# CANFLYSKY.net
KiCad netlist of a schematic drawn in EAGLE
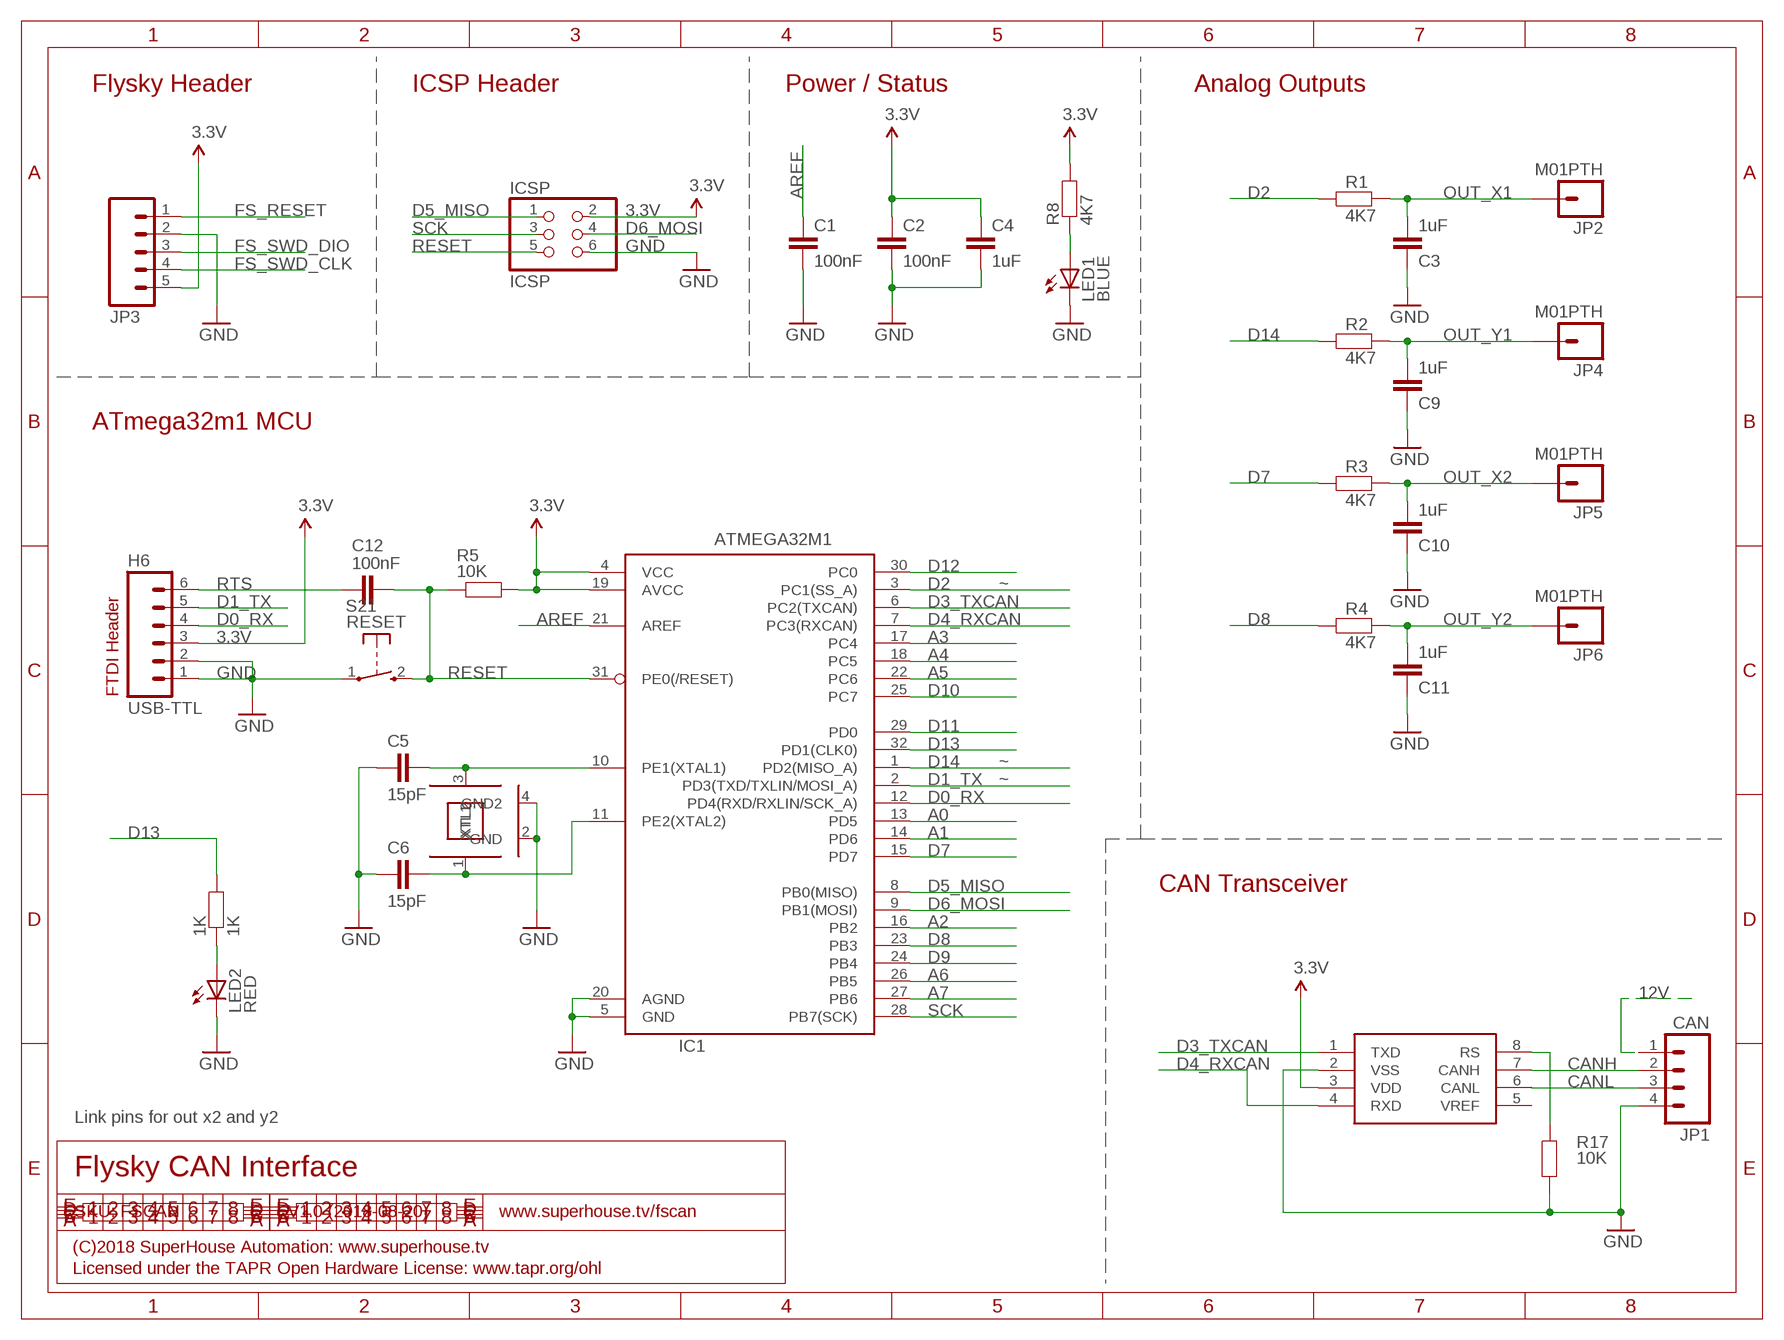
[diagram p0: schematic, sheet 1]

(export (version "E")
  (design (tool "Eeschema 10.0.6"))
  (components
    (comp (ref "1K")
      (value "1K")
      (footprint "eagle-import:0603")
      (libsource (lib "eagle-import") (part "RESISTOR0603"))
    )
    (comp (ref "C1")
      (value "100nF")
      (footprint "eagle-import:0603")
      (libsource (lib "eagle-import") (part "CAP0603"))
    )
    (comp (ref "C2")
      (value "100nF")
      (footprint "eagle-import:0603")
      (libsource (lib "eagle-import") (part "CAP0603"))
    )
    (comp (ref "C3")
      (value "1uF")
      (footprint "eagle-import:0603")
      (libsource (lib "eagle-import") (part "CAP0603"))
    )
    (comp (ref "C4")
      (value "1uF")
      (footprint "eagle-import:0603")
      (libsource (lib "eagle-import") (part "CAP0603"))
    )
    (comp (ref "C5")
      (value "15pF")
      (footprint "eagle-import:0603")
      (libsource (lib "eagle-import") (part "CAP0603"))
    )
    (comp (ref "C6")
      (value "15pF")
      (footprint "eagle-import:0603")
      (libsource (lib "eagle-import") (part "CAP0603"))
    )
    (comp (ref "C9")
      (value "1uF")
      (footprint "eagle-import:0603")
      (libsource (lib "eagle-import") (part "CAP0603"))
    )
    (comp (ref "C10")
      (value "1uF")
      (footprint "eagle-import:0603")
      (libsource (lib "eagle-import") (part "CAP0603"))
    )
    (comp (ref "C11")
      (value "1uF")
      (footprint "eagle-import:0603")
      (libsource (lib "eagle-import") (part "CAP0603"))
    )
    (comp (ref "C12")
      (value "100nF")
      (footprint "eagle-import:0603")
      (libsource (lib "eagle-import") (part "CAP0603"))
    )
    (comp (ref "H6")
      (value "USB-TTL")
      (footprint "eagle-import:1X06")
      (libsource (lib "eagle-import") (part "M06SIP"))
    )
    (comp (ref "IC1")
      (value "ATMEGA32M1")
      (footprint "eagle-import:TQFP32-08")
      (libsource (lib "eagle-import") (part "ATMEGA32M1"))
    )
    (comp (ref "ICSP")
      (value "ICSP")
      (footprint "eagle-import:2X03")
      (libsource (lib "eagle-import") (part "PINHD-2X3"))
    )
    (comp (ref "JP1")
      (value "CAN")
      (footprint "eagle-import:1X04")
      (libsource (lib "eagle-import") (part "M04PTH"))
    )
    (comp (ref "JP2")
      (value "M01PTH")
      (footprint "eagle-import:1X01")
      (libsource (lib "eagle-import") (part "M01PTH"))
    )
    (comp (ref "JP3")
      (value "M05PTH")
      (footprint "eagle-import:1X05")
      (libsource (lib "eagle-import") (part "M05PTH"))
    )
    (comp (ref "JP4")
      (value "M01PTH")
      (footprint "eagle-import:1X01")
      (libsource (lib "eagle-import") (part "M01PTH"))
    )
    (comp (ref "JP5")
      (value "M01PTH")
      (footprint "eagle-import:1X01")
      (libsource (lib "eagle-import") (part "M01PTH"))
    )
    (comp (ref "JP6")
      (value "M01PTH")
      (footprint "eagle-import:1X01")
      (libsource (lib "eagle-import") (part "M01PTH"))
    )
    (comp (ref "LED1")
      (value "BLUE")
      (footprint "eagle-import:LED-0603")
      (libsource (lib "eagle-import") (part "LED0603"))
    )
    (comp (ref "LED2")
      (value "RED")
      (footprint "eagle-import:LED-0603")
      (libsource (lib "eagle-import") (part "LED0603"))
    )
    (comp (ref "R1")
      (value "4K7")
      (footprint "eagle-import:0603")
      (libsource (lib "eagle-import") (part "freetronics-master-v1.1_RESISTOR0603"))
    )
    (comp (ref "R2")
      (value "4K7")
      (footprint "eagle-import:0603")
      (libsource (lib "eagle-import") (part "freetronics-master-v1.1_RESISTOR0603"))
    )
    (comp (ref "R3")
      (value "4K7")
      (footprint "eagle-import:0603")
      (libsource (lib "eagle-import") (part "freetronics-master-v1.1_RESISTOR0603"))
    )
    (comp (ref "R4")
      (value "4K7")
      (footprint "eagle-import:0603")
      (libsource (lib "eagle-import") (part "freetronics-master-v1.1_RESISTOR0603"))
    )
    (comp (ref "R5")
      (value "10K")
      (footprint "eagle-import:0603")
      (libsource (lib "eagle-import") (part "freetronics-master-v1.1_RESISTOR0603"))
    )
    (comp (ref "R8")
      (value "4K7")
      (footprint "eagle-import:0603")
      (libsource (lib "eagle-import") (part "RESISTOR0603"))
    )
    (comp (ref "R17")
      (value "10K")
      (footprint "eagle-import:0603")
      (libsource (lib "eagle-import") (part "freetronics-master-v1.1_RESISTOR0603"))
    )
    (comp (ref "S21")
      (value "RESET")
      (footprint "eagle-import:TACTILE_SWITCH_SMD_2PIN_TINY")
      (libsource (lib "eagle-import") (part "TAC_SWITCH_2PINSMT"))
    )
    (comp (ref "U1")
      (value "MCP2551")
      (footprint "eagle-import:SO08")
      (libsource (lib "eagle-import") (part "MCP2551"))
    )
    (comp (ref "XTL1")
      (value "8MHz")
      (footprint "eagle-import:CRYSTAL-SMD-3X2")
      (libsource (lib "eagle-import") (part "CRYSTAL-GND3X2"))
    )
  )
  (nets
    (net (code "1") (name "/12V") (class "Default")
      (node (ref "JP1") (pin "1") (pinfunction "1_1") (pintype "passive"))
    )
    (net (code "2") (name "/A0") (class "Default")
      (node (ref "IC1") (pin "13") (pinfunction "PD5_13") (pintype "bidirectional"))
    )
    (net (code "3") (name "/A1") (class "Default")
      (node (ref "IC1") (pin "14") (pinfunction "PD6_14") (pintype "bidirectional"))
    )
    (net (code "4") (name "/A2") (class "Default")
      (node (ref "IC1") (pin "16") (pinfunction "PB2_16") (pintype "bidirectional"))
    )
    (net (code "5") (name "/A3") (class "Default")
      (node (ref "IC1") (pin "17") (pinfunction "PC4_17") (pintype "bidirectional"))
    )
    (net (code "6") (name "/A4") (class "Default")
      (node (ref "IC1") (pin "18") (pinfunction "PC5_18") (pintype "bidirectional"))
    )
    (net (code "7") (name "/A5") (class "Default")
      (node (ref "IC1") (pin "22") (pinfunction "PC6_22") (pintype "bidirectional"))
    )
    (net (code "8") (name "/A6") (class "Default")
      (node (ref "IC1") (pin "26") (pinfunction "PB5_26") (pintype "bidirectional"))
    )
    (net (code "9") (name "/A7") (class "Default")
      (node (ref "IC1") (pin "27") (pinfunction "PB6_27") (pintype "bidirectional"))
    )
    (net (code "10") (name "/AREF") (class "Default")
      (node (ref "C1") (pin "1") (pinfunction "1_1") (pintype "passive"))
      (node (ref "IC1") (pin "21") (pinfunction "AREF_21") (pintype "bidirectional"))
    )
    (net (code "11") (name "/CANH") (class "Default")
      (node (ref "JP1") (pin "2") (pinfunction "2_2") (pintype "passive"))
      (node (ref "U1") (pin "7") (pinfunction "CANH_7") (pintype "bidirectional"))
    )
    (net (code "12") (name "/CANL") (class "Default")
      (node (ref "JP1") (pin "3") (pinfunction "3_3") (pintype "passive"))
      (node (ref "U1") (pin "6") (pinfunction "CANL_6") (pintype "bidirectional"))
    )
    (net (code "13") (name "/D0_RX") (class "Default")
      (node (ref "H6") (pin "4") (pinfunction "4_4") (pintype "passive"))
      (node (ref "IC1") (pin "12") (pinfunction "PD4(RXD/RXLIN/SCK_A)_12") (pintype "bidirectional"))
    )
    (net (code "14") (name "/D1_TX") (class "Default")
      (node (ref "H6") (pin "5") (pinfunction "5_5") (pintype "passive"))
      (node (ref "IC1") (pin "2") (pinfunction "PD3(TXD/TXLIN/MOSI_A)_2") (pintype "bidirectional"))
    )
    (net (code "15") (name "/D2") (class "Default")
      (node (ref "IC1") (pin "3") (pinfunction "PC1(SS_A)_3") (pintype "bidirectional"))
      (node (ref "R1") (pin "1") (pinfunction "1_1") (pintype "passive"))
    )
    (net (code "16") (name "/D3_TXCAN") (class "Default")
      (node (ref "IC1") (pin "6") (pinfunction "PC2(TXCAN)_6") (pintype "bidirectional"))
      (node (ref "U1") (pin "1") (pinfunction "TXD_1") (pintype "bidirectional"))
    )
    (net (code "17") (name "/D4_RXCAN") (class "Default")
      (node (ref "IC1") (pin "7") (pinfunction "PC3(RXCAN)_7") (pintype "bidirectional"))
      (node (ref "U1") (pin "4") (pinfunction "RXD_4") (pintype "bidirectional"))
    )
    (net (code "18") (name "/D5_MISO") (class "Default")
      (node (ref "IC1") (pin "8") (pinfunction "PB0(MISO)_8") (pintype "bidirectional"))
      (node (ref "ICSP") (pin "1") (pinfunction "1_1") (pintype "passive"))
    )
    (net (code "19") (name "/D6_MOSI") (class "Default")
      (node (ref "IC1") (pin "9") (pinfunction "PB1(MOSI)_9") (pintype "bidirectional"))
      (node (ref "ICSP") (pin "4") (pinfunction "4_4") (pintype "passive"))
    )
    (net (code "20") (name "/D7") (class "Default")
      (node (ref "IC1") (pin "15") (pinfunction "PD7_15") (pintype "bidirectional"))
      (node (ref "R3") (pin "1") (pinfunction "1_1") (pintype "passive"))
    )
    (net (code "21") (name "/D8") (class "Default")
      (node (ref "IC1") (pin "23") (pinfunction "PB3_23") (pintype "bidirectional"))
      (node (ref "R4") (pin "1") (pinfunction "1_1") (pintype "passive"))
    )
    (net (code "22") (name "/D9") (class "Default")
      (node (ref "IC1") (pin "24") (pinfunction "PB4_24") (pintype "bidirectional"))
    )
    (net (code "23") (name "/D10") (class "Default")
      (node (ref "IC1") (pin "25") (pinfunction "PC7_25") (pintype "bidirectional"))
    )
    (net (code "24") (name "/D11") (class "Default")
      (node (ref "IC1") (pin "29") (pinfunction "PD0_29") (pintype "bidirectional"))
    )
    (net (code "25") (name "/D12") (class "Default")
      (node (ref "IC1") (pin "30") (pinfunction "PC0_30") (pintype "bidirectional"))
    )
    (net (code "26") (name "/D13") (class "Default")
      (node (ref "1K") (pin "2") (pinfunction "2_2") (pintype "passive"))
      (node (ref "IC1") (pin "32") (pinfunction "PD1(CLK0)_32") (pintype "bidirectional"))
    )
    (net (code "27") (name "/D14") (class "Default")
      (node (ref "IC1") (pin "1") (pinfunction "PD2(MISO_A)_1") (pintype "bidirectional"))
      (node (ref "R2") (pin "1") (pinfunction "1_1") (pintype "passive"))
    )
    (net (code "28") (name "/FS_RESET") (class "Default")
      (node (ref "JP3") (pin "1") (pinfunction "1_1") (pintype "passive"))
    )
    (net (code "29") (name "/FS_SWD_CLK") (class "Default")
      (node (ref "JP3") (pin "4") (pinfunction "4_4") (pintype "passive"))
    )
    (net (code "30") (name "/FS_SWD_DIO") (class "Default")
      (node (ref "JP3") (pin "3") (pinfunction "3_3") (pintype "passive"))
    )
    (net (code "31") (name "/OUT_X1") (class "Default")
      (node (ref "C3") (pin "1") (pinfunction "1_1") (pintype "passive"))
      (node (ref "JP2") (pin "1") (pinfunction "1_1") (pintype "passive"))
      (node (ref "R1") (pin "2") (pinfunction "2_2") (pintype "passive"))
    )
    (net (code "32") (name "/OUT_X2") (class "Default")
      (node (ref "C10") (pin "1") (pinfunction "1_1") (pintype "passive"))
      (node (ref "JP5") (pin "1") (pinfunction "1_1") (pintype "passive"))
      (node (ref "R3") (pin "2") (pinfunction "2_2") (pintype "passive"))
    )
    (net (code "33") (name "/OUT_Y1") (class "Default")
      (node (ref "C9") (pin "1") (pinfunction "1_1") (pintype "passive"))
      (node (ref "JP4") (pin "1") (pinfunction "1_1") (pintype "passive"))
      (node (ref "R2") (pin "2") (pinfunction "2_2") (pintype "passive"))
    )
    (net (code "34") (name "/OUT_Y2") (class "Default")
      (node (ref "C11") (pin "1") (pinfunction "1_1") (pintype "passive"))
      (node (ref "JP6") (pin "1") (pinfunction "1_1") (pintype "passive"))
      (node (ref "R4") (pin "2") (pinfunction "2_2") (pintype "passive"))
    )
    (net (code "35") (name "/RESET") (class "Default")
      (node (ref "C12") (pin "2") (pinfunction "2_2") (pintype "passive"))
      (node (ref "IC1") (pin "31") (pinfunction "PE0(/RESET)_31") (pintype "bidirectional"))
      (node (ref "ICSP") (pin "5") (pinfunction "5_5") (pintype "passive"))
      (node (ref "R5") (pin "2") (pinfunction "2_2") (pintype "passive"))
      (node (ref "S21") (pin "2") (pinfunction "S_2") (pintype "passive"))
    )
    (net (code "36") (name "/RTS") (class "Default")
      (node (ref "C12") (pin "1") (pinfunction "1_1") (pintype "passive"))
      (node (ref "H6") (pin "6") (pinfunction "6_6") (pintype "passive"))
    )
    (net (code "37") (name "/SCK") (class "Default")
      (node (ref "IC1") (pin "28") (pinfunction "PB7(SCK)_28") (pintype "bidirectional"))
      (node (ref "ICSP") (pin "3") (pinfunction "3_3") (pintype "passive"))
    )
    (net (code "38") (name "3.3V") (class "Default")
      (node (ref "C2") (pin "1") (pinfunction "1_1") (pintype "passive"))
      (node (ref "C4") (pin "1") (pinfunction "1_1") (pintype "passive"))
      (node (ref "H6") (pin "3") (pinfunction "3_3") (pintype "passive"))
      (node (ref "IC1") (pin "19") (pinfunction "AVCC_19") (pintype "bidirectional"))
      (node (ref "IC1") (pin "4") (pinfunction "VCC_4") (pintype "bidirectional"))
      (node (ref "ICSP") (pin "2") (pinfunction "2_2") (pintype "passive"))
      (node (ref "JP3") (pin "5") (pinfunction "5_5") (pintype "passive"))
      (node (ref "R5") (pin "1") (pinfunction "1_1") (pintype "passive"))
      (node (ref "R8") (pin "2") (pinfunction "2_2") (pintype "passive"))
      (node (ref "U1") (pin "3") (pinfunction "VDD_3") (pintype "bidirectional"))
    )
    (net (code "39") (name "GND") (class "Default")
      (node (ref "C1") (pin "2") (pinfunction "2_2") (pintype "passive"))
      (node (ref "C10") (pin "2") (pinfunction "2_2") (pintype "passive"))
      (node (ref "C11") (pin "2") (pinfunction "2_2") (pintype "passive"))
      (node (ref "C2") (pin "2") (pinfunction "2_2") (pintype "passive"))
      (node (ref "C3") (pin "2") (pinfunction "2_2") (pintype "passive"))
      (node (ref "C4") (pin "2") (pinfunction "2_2") (pintype "passive"))
      (node (ref "C5") (pin "1") (pinfunction "1_1") (pintype "passive"))
      (node (ref "C6") (pin "1") (pinfunction "1_1") (pintype "passive"))
      (node (ref "C9") (pin "2") (pinfunction "2_2") (pintype "passive"))
      (node (ref "H6") (pin "1") (pinfunction "1_1") (pintype "passive"))
      (node (ref "H6") (pin "2") (pinfunction "2_2") (pintype "passive"))
      (node (ref "IC1") (pin "20") (pinfunction "AGND_20") (pintype "bidirectional"))
      (node (ref "IC1") (pin "5") (pinfunction "GND_5") (pintype "bidirectional"))
      (node (ref "ICSP") (pin "6") (pinfunction "6_6") (pintype "passive"))
      (node (ref "JP1") (pin "4") (pinfunction "4_4") (pintype "passive"))
      (node (ref "JP3") (pin "2") (pinfunction "2_2") (pintype "passive"))
      (node (ref "LED1") (pin "C") (pinfunction "C_C") (pintype "passive"))
      (node (ref "LED2") (pin "C") (pinfunction "C_C") (pintype "passive"))
      (node (ref "R17") (pin "1") (pinfunction "1_1") (pintype "passive"))
      (node (ref "S21") (pin "1") (pinfunction "P_1") (pintype "passive"))
      (node (ref "U1") (pin "2") (pinfunction "VSS_2") (pintype "bidirectional"))
      (node (ref "XTL1") (pin "2") (pinfunction "GND_2") (pintype "bidirectional"))
      (node (ref "XTL1") (pin "4") (pinfunction "GND2_4") (pintype "bidirectional"))
    )
    (net (code "40") (name "Net-(1K-Pad1)") (class "Default")
      (node (ref "1K") (pin "1") (pinfunction "1_1") (pintype "passive"))
      (node (ref "LED2") (pin "A") (pinfunction "A_A") (pintype "passive"))
    )
    (net (code "41") (name "Net-(IC1-PE1(XTAL1))") (class "Default")
      (node (ref "C5") (pin "2") (pinfunction "2_2") (pintype "passive"))
      (node (ref "IC1") (pin "10") (pinfunction "PE1(XTAL1)_10") (pintype "bidirectional"))
      (node (ref "XTL1") (pin "3") (pinfunction "XTL2_3") (pintype "bidirectional"))
    )
    (net (code "42") (name "Net-(IC1-PE2(XTAL2))") (class "Default")
      (node (ref "C6") (pin "2") (pinfunction "2_2") (pintype "passive"))
      (node (ref "IC1") (pin "11") (pinfunction "PE2(XTAL2)_11") (pintype "bidirectional"))
      (node (ref "XTL1") (pin "1") (pinfunction "XTL1_1") (pintype "bidirectional"))
    )
    (net (code "43") (name "Net-(LED1-PadA)") (class "Default")
      (node (ref "LED1") (pin "A") (pinfunction "A_A") (pintype "passive"))
      (node (ref "R8") (pin "1") (pinfunction "1_1") (pintype "passive"))
    )
    (net (code "44") (name "Net-(U1-RS)") (class "Default")
      (node (ref "R17") (pin "2") (pinfunction "2_2") (pintype "passive"))
      (node (ref "U1") (pin "8") (pinfunction "RS_8") (pintype "bidirectional"))
    )
    (net (code "45") (name "unconnected-(U1-VREF-Pad5)") (class "Default")
      (node (ref "U1") (pin "5") (pinfunction "VREF_5") (pintype "bidirectional"))
    )
  )
)
